# Sheet2.net
KiCad netlist of a schematic drawn in Altium Designer
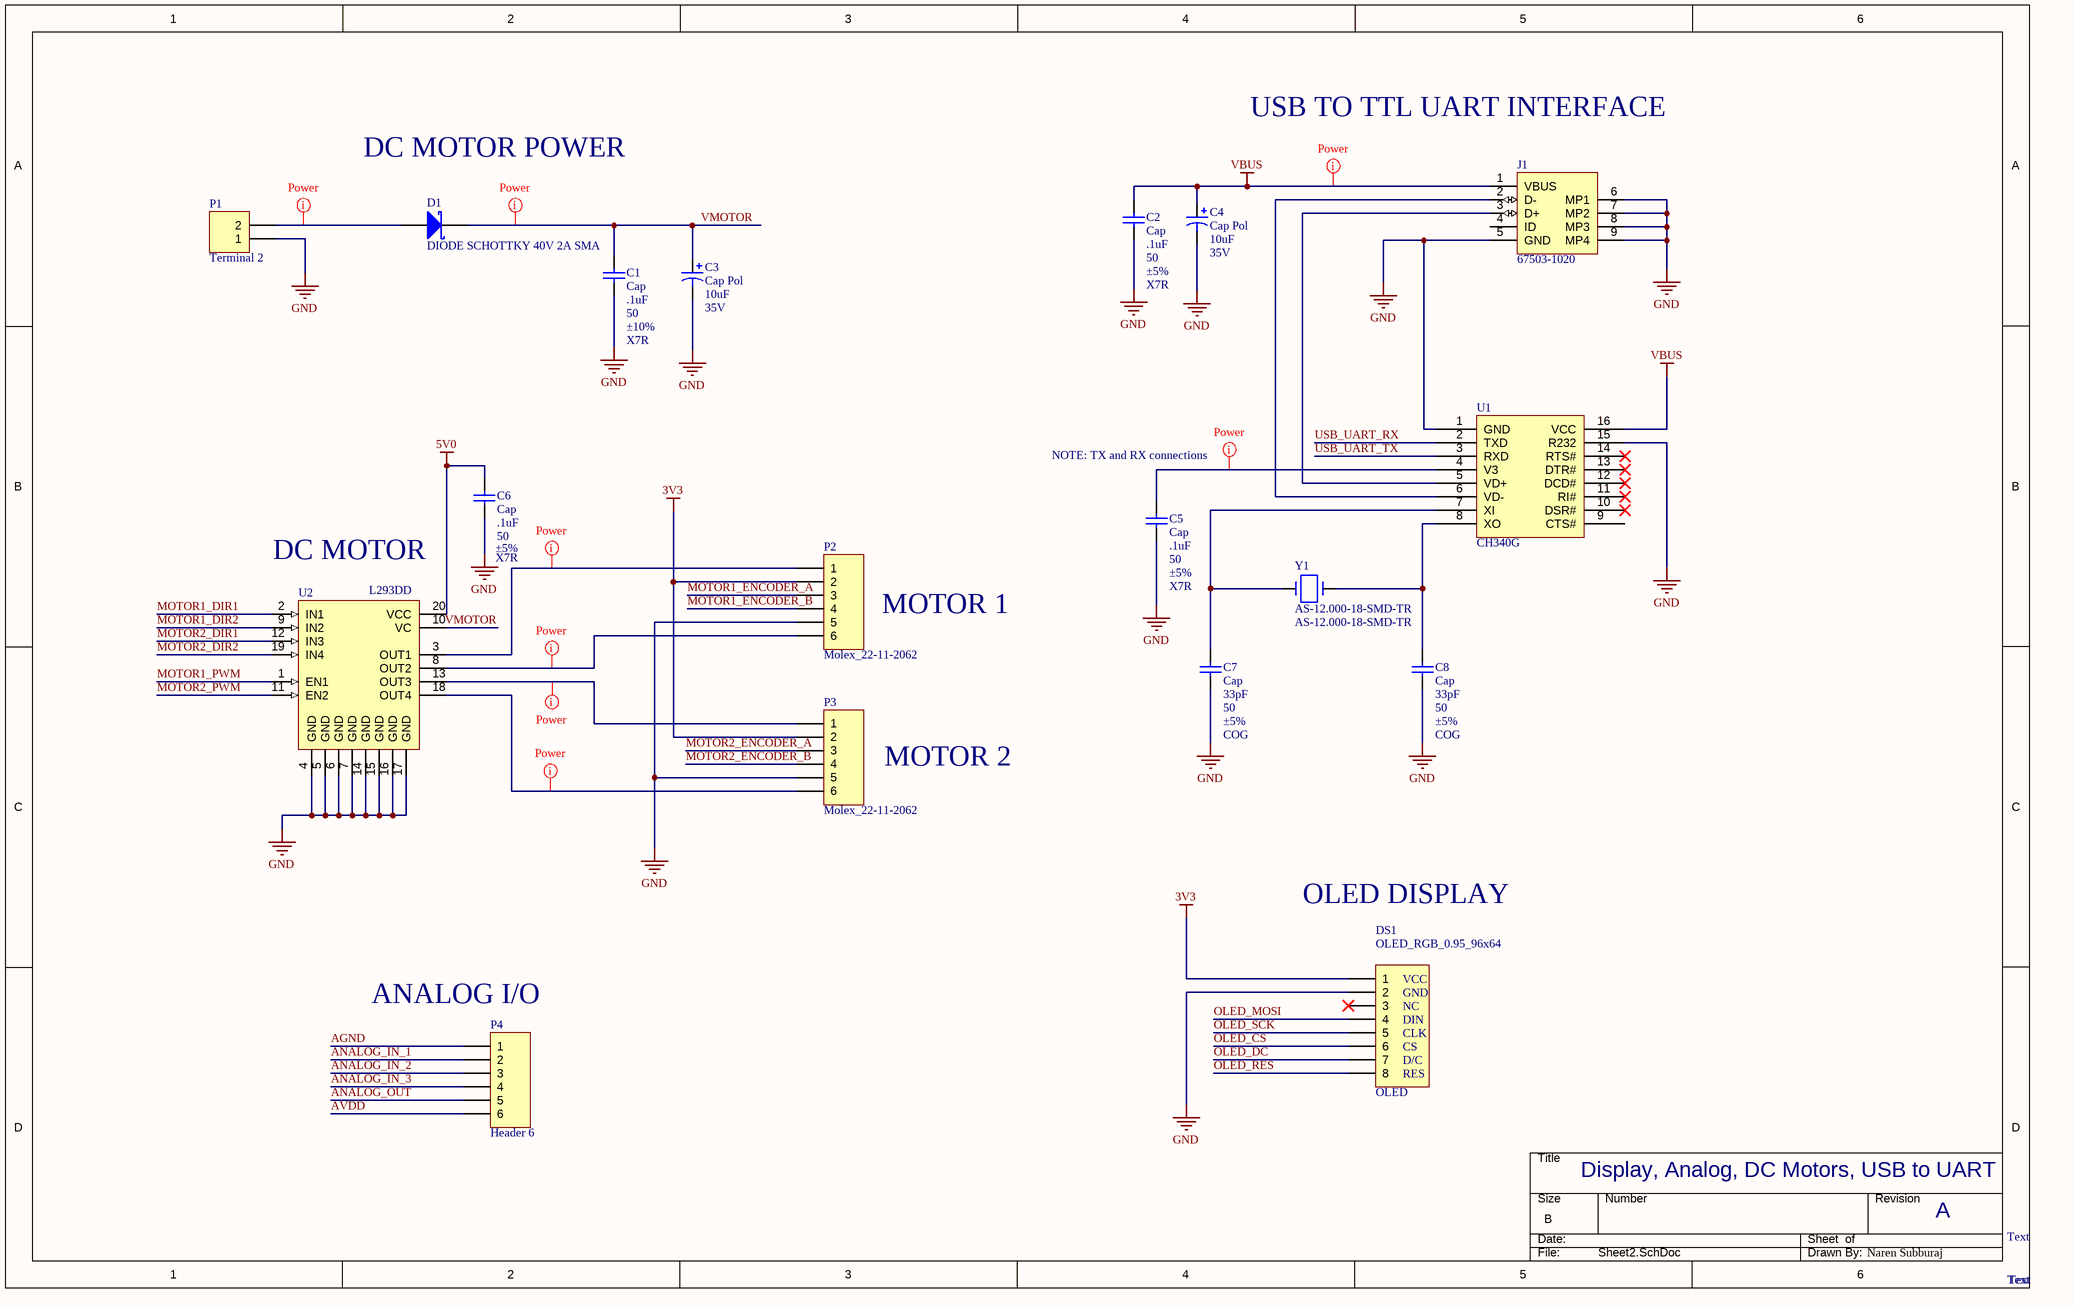
[diagram p0: Sheet2.SchDoc]

(export (version "E")
  (design (tool "Eeschema 10.0.6"))
  (components
    (comp (ref "C1")
      (value "Cap")
      (footprint "CAPC2012X09M")
      (description "CAP CER .1uF 50v X7R 0805")
      (fields
        (field (name "ALTIUM_VALUE") ".1uF")
        (field (name "WV") "50")
        (field (name "TOLERANCE") "±10%")
        (field (name "TYPE") "X7R")
        (field (name "MPN") "C0805C104K5RACTU")
      )
      (libsource (lib "esd_library") (part "CAP-X7R-.1uF-50V-±10%"))
    )
    (comp (ref "C2")
      (value "Cap")
      (footprint "CAPC2012X09M")
      (description "CAP CER .1uF 50v X7R 0805")
      (fields
        (field (name "ALTIUM_VALUE") ".1uF")
        (field (name "WV") "50")
        (field (name "TOLERANCE") "±5%")
        (field (name "TYPE") "X7R")
        (field (name "MPN") "C0805C104J5RACTU")
      )
      (libsource (lib "esd_library") (part "CAP-X7R-.1uF-50V-±5%"))
    )
    (comp (ref "C3")
      (value "Cap Pol")
      (footprint "CAPACITOR_5MM")
      (description "CAP 85C 10uF ±20% 35V WX Series Aluminum Electrolytic")
      (fields
        (field (name "ALTIUM_VALUE") "10uF")
        (field (name "VOLTAGE") "35V")
        (field (name "MPN") "UWX1V100MCL1GB")
      )
      (libsource (lib "esd_library") (part "Cap Polar-10uF-35V"))
    )
    (comp (ref "C4")
      (value "Cap Pol")
      (footprint "CAPACITOR_5MM")
      (description "CAP 85C 10uF ±20% 35V WX Series Aluminum Electrolytic")
      (fields
        (field (name "ALTIUM_VALUE") "10uF")
        (field (name "VOLTAGE") "35V")
        (field (name "MPN") "UWX1V100MCL1GB")
      )
      (libsource (lib "esd_library") (part "Cap Polar-10uF-35V"))
    )
    (comp (ref "C5")
      (value "Cap")
      (footprint "CAPC2012X09M")
      (description "CAP CER .1uF 50v X7R 0805")
      (fields
        (field (name "ALTIUM_VALUE") ".1uF")
        (field (name "WV") "50")
        (field (name "TOLERANCE") "±5%")
        (field (name "TYPE") "X7R")
        (field (name "MPN") "C0805C104J5RACTU")
      )
      (libsource (lib "esd_library") (part "CAP-X7R-.1uF-50V-±5%"))
    )
    (comp (ref "C6")
      (value "Cap")
      (footprint "CAPC2012X09M")
      (description "CAP CER .1uF 50v X7R 0805")
      (fields
        (field (name "ALTIUM_VALUE") ".1uF")
        (field (name "WV") "50")
        (field (name "TOLERANCE") "±5%")
        (field (name "TYPE") "X7R")
        (field (name "MPN") "C0805C104J5RACTU")
      )
      (libsource (lib "esd_library") (part "CAP-X7R-.1uF-50V-±5%"))
    )
    (comp (ref "C7")
      (value "Cap")
      (footprint "CAPC2012X09M")
      (description "CAP CER 33pF 50v COG 0805")
      (fields
        (field (name "ALTIUM_VALUE") "33pF")
        (field (name "WV") "50")
        (field (name "TOLERANCE") "±5%")
        (field (name "TYPE") "COG")
        (field (name "MPN") "C0805C330J5GACTU")
      )
      (libsource (lib "esd_library") (part "CAP-COG-33pF-50V-±5%"))
    )
    (comp (ref "C8")
      (value "Cap")
      (footprint "CAPC2012X09M")
      (description "CAP CER 33pF 50v COG 0805")
      (fields
        (field (name "ALTIUM_VALUE") "33pF")
        (field (name "WV") "50")
        (field (name "TOLERANCE") "±5%")
        (field (name "TYPE") "COG")
        (field (name "MPN") "C0805C330J5GACTU")
      )
      (libsource (lib "esd_library") (part "CAP-COG-33pF-50V-±5%"))
    )
    (comp (ref "D1")
      (value "DIODE SCHOTTKY 40V 2A SMA")
      (footprint "DIOM4326X23M")
      (description "Schottky Rectifier")
      (fields (field (name "MPN") "B240A-13-F"))
      (libsource (lib "esd_library") (part "DIODE SCHOTTKY 40V 2A SMA"))
    )
    (comp (ref "DS1")
      (value "OLED")
      (footprint "OLED_RGB_0.95_96x64_Waveshare")
      (description "Waveshare 0.95 inch OLED Module")
      (fields (field (name "MPN") "PPPC081LFBN-RC"))
      (libsource (lib "esd_library") (part "OLED_RGB_0.95_96x64_Waveshare"))
    )
    (comp (ref "J1")
      (value "67503-1020")
      (footprint "MOLX-67503-1020_V")
      (description "USB, MINI, SMD, RA KME04-USBMU03A01")
      (fields (field (name "MANUFACTURER") "Molex"))
      (libsource (lib "esd_library") (part "MOLX-67503-1020"))
    )
    (comp (ref "P1")
      (value "Terminal 2")
      (footprint "TYCO_282841_2")
      (description "Terminal, 2-Pin")
      (fields (field (name "MPN") "282841-2") (field (name "PUBLISHER") "Altium Limited"))
      (libsource (lib "esd_library") (part "Terminal 2"))
    )
    (comp (ref "P2")
      (value "Molex_22-11-2062")
      (footprint "MOLEX_22-11-2062")
      (description "CONN HEADER 6POS .100 VERT GOLD")
      (fields (field (name "MPN") "0022112062"))
      (libsource (lib "esd_library") (part "Molex_22-11-2062"))
    )
    (comp (ref "P3")
      (value "Molex_22-11-2062")
      (footprint "MOLEX_22-11-2062")
      (description "CONN HEADER 6POS .100 VERT GOLD")
      (fields (field (name "MPN") "0022112062"))
      (libsource (lib "esd_library") (part "Molex_22-11-2062"))
    )
    (comp (ref "P4")
      (value "Header 6")
      (footprint "HDR1X6")
      (description "Header, 6-Pin Male")
      (fields (field (name "MPN") "PEC06SFAN"))
      (libsource (lib "esd_library") (part "Header 6"))
    )
    (comp (ref "U1")
      (value "CH340G")
      (footprint "NSO16_L")
      (description "USB to serial chip")
      (libsource (lib "esd_library") (part "CH340G"))
    )
    (comp (ref "U2")
      (value "L293DD")
      (footprint "SO20_N")
      (description "IC MOTOR DRIVER PAR 20-SOIC")
      (fields (field (name "MPN") "L293DD013TR") (field (name "PUBLISHER") "Altium Limited"))
      (libsource (lib "esd_library") (part "L293DD"))
    )
    (comp (ref "Y1")
      (value "AS-12.000-18-SMD-TR")
      (footprint "HCS-49/U")
      (description "CRYSTAL 12.0000MHZ 18PF SMD")
      (fields (field (name "MPN") "AS-12.000-18-SMD-TR"))
      (libsource (lib "esd_library") (part "AS-12.000-18-SMD-TR"))
    )
  )
  (nets
    (net (code "1") (name "/AGND") (class "Default")
      (node (ref "P4") (pin "1") (pinfunction "1_1") (pintype "passive"))
    )
    (net (code "2") (name "/ANALOG_IN_1") (class "Default")
      (node (ref "P4") (pin "2") (pinfunction "2_2") (pintype "passive"))
    )
    (net (code "3") (name "/ANALOG_IN_2") (class "Default")
      (node (ref "P4") (pin "3") (pinfunction "3_3") (pintype "passive"))
    )
    (net (code "4") (name "/ANALOG_IN_3") (class "Default")
      (node (ref "P4") (pin "4") (pinfunction "4_4") (pintype "passive"))
    )
    (net (code "5") (name "/ANALOG_OUT") (class "Default")
      (node (ref "P4") (pin "5") (pinfunction "5_5") (pintype "passive"))
    )
    (net (code "6") (name "/AVDD") (class "Default")
      (node (ref "P4") (pin "6") (pinfunction "6_6") (pintype "passive"))
    )
    (net (code "7") (name "/MOTOR1_DIR1") (class "Default")
      (node (ref "U2") (pin "2") (pinfunction "IN1_2") (pintype "input"))
    )
    (net (code "8") (name "/MOTOR1_DIR2") (class "Default")
      (node (ref "U2") (pin "9") (pinfunction "IN2_9") (pintype "input"))
    )
    (net (code "9") (name "/MOTOR1_ENCODER_A") (class "Default")
      (node (ref "P2") (pin "3") (pinfunction "3_3") (pintype "passive"))
    )
    (net (code "10") (name "/MOTOR1_ENCODER_B") (class "Default")
      (node (ref "P2") (pin "4") (pinfunction "4_4") (pintype "passive"))
    )
    (net (code "11") (name "/MOTOR1_PWM") (class "Default")
      (node (ref "U2") (pin "1") (pinfunction "EN1_1") (pintype "input"))
    )
    (net (code "12") (name "/MOTOR2_DIR1") (class "Default")
      (node (ref "U2") (pin "12") (pinfunction "IN3_12") (pintype "input"))
    )
    (net (code "13") (name "/MOTOR2_DIR2") (class "Default")
      (node (ref "U2") (pin "19") (pinfunction "IN4_19") (pintype "input"))
    )
    (net (code "14") (name "/MOTOR2_ENCODER_A") (class "Default")
      (node (ref "P3") (pin "3") (pinfunction "3_3") (pintype "passive"))
    )
    (net (code "15") (name "/MOTOR2_ENCODER_B") (class "Default")
      (node (ref "P3") (pin "4") (pinfunction "4_4") (pintype "passive"))
    )
    (net (code "16") (name "/MOTOR2_PWM") (class "Default")
      (node (ref "U2") (pin "11") (pinfunction "EN2_11") (pintype "input"))
    )
    (net (code "17") (name "/OLED_CS") (class "Default")
      (node (ref "DS1") (pin "6") (pinfunction "6_6") (pintype "passive"))
    )
    (net (code "18") (name "/OLED_DC") (class "Default")
      (node (ref "DS1") (pin "7") (pinfunction "7_7") (pintype "passive"))
    )
    (net (code "19") (name "/OLED_MOSI") (class "Default")
      (node (ref "DS1") (pin "4") (pinfunction "4_4") (pintype "passive"))
    )
    (net (code "20") (name "/OLED_RES") (class "Default")
      (node (ref "DS1") (pin "8") (pinfunction "8_8") (pintype "passive"))
    )
    (net (code "21") (name "/OLED_SCK") (class "Default")
      (node (ref "DS1") (pin "5") (pinfunction "5_5") (pintype "passive"))
    )
    (net (code "22") (name "/USB_UART_RX") (class "Default")
      (node (ref "U1") (pin "2") (pinfunction "TXD_2") (pintype "passive"))
    )
    (net (code "23") (name "/USB_UART_TX") (class "Default")
      (node (ref "U1") (pin "3") (pinfunction "RXD_3") (pintype "passive"))
    )
    (net (code "24") (name "/VMOTOR") (class "Default")
      (node (ref "C1") (pin "2") (pinfunction "2_2") (pintype "passive"))
      (node (ref "C3") (pin "1") (pinfunction "1_1") (pintype "passive"))
      (node (ref "D1") (pin "1") (pinfunction "K_1") (pintype "passive"))
      (node (ref "U2") (pin "10") (pinfunction "VC_10") (pintype "power_in"))
    )
    (net (code "25") (name "3V3") (class "Default")
      (node (ref "DS1") (pin "1") (pinfunction "1_1") (pintype "passive"))
      (node (ref "P2") (pin "2") (pinfunction "2_2") (pintype "passive"))
      (node (ref "P3") (pin "2") (pinfunction "2_2") (pintype "passive"))
    )
    (net (code "26") (name "5V0") (class "Default")
      (node (ref "C6") (pin "2") (pinfunction "2_2") (pintype "passive"))
      (node (ref "U2") (pin "20") (pinfunction "VCC_20") (pintype "power_in"))
    )
    (net (code "27") (name "GND") (class "Default")
      (node (ref "C1") (pin "1") (pinfunction "1_1") (pintype "passive"))
      (node (ref "C2") (pin "2") (pinfunction "2_2") (pintype "passive"))
      (node (ref "C3") (pin "2") (pinfunction "2_2") (pintype "passive"))
      (node (ref "C4") (pin "2") (pinfunction "2_2") (pintype "passive"))
      (node (ref "C5") (pin "2") (pinfunction "2_2") (pintype "passive"))
      (node (ref "C6") (pin "1") (pinfunction "1_1") (pintype "passive"))
      (node (ref "C7") (pin "2") (pinfunction "2_2") (pintype "passive"))
      (node (ref "C8") (pin "2") (pinfunction "2_2") (pintype "passive"))
      (node (ref "DS1") (pin "2") (pinfunction "2_2") (pintype "passive"))
      (node (ref "J1") (pin "5") (pinfunction "GND_5") (pintype "power_in"))
      (node (ref "J1") (pin "6") (pinfunction "MP1_6") (pintype "passive"))
      (node (ref "J1") (pin "7") (pinfunction "MP2_7") (pintype "passive"))
      (node (ref "J1") (pin "8") (pinfunction "MP3_8") (pintype "passive"))
      (node (ref "J1") (pin "9") (pinfunction "MP4_9") (pintype "passive"))
      (node (ref "P1") (pin "1") (pinfunction "1_1") (pintype "passive"))
      (node (ref "P2") (pin "5") (pinfunction "5_5") (pintype "passive"))
      (node (ref "P3") (pin "5") (pinfunction "5_5") (pintype "passive"))
      (node (ref "U1") (pin "1") (pinfunction "GND_1") (pintype "passive"))
      (node (ref "U1") (pin "15") (pinfunction "R232_15") (pintype "passive"))
      (node (ref "U2") (pin "14") (pinfunction "GND_14") (pintype "power_in"))
      (node (ref "U2") (pin "15") (pinfunction "GND_15") (pintype "power_in"))
      (node (ref "U2") (pin "16") (pinfunction "GND_16") (pintype "power_in"))
      (node (ref "U2") (pin "17") (pinfunction "GND_17") (pintype "power_in"))
      (node (ref "U2") (pin "4") (pinfunction "GND_4") (pintype "power_in"))
      (node (ref "U2") (pin "5") (pinfunction "GND_5") (pintype "power_in"))
      (node (ref "U2") (pin "6") (pinfunction "GND_6") (pintype "power_in"))
      (node (ref "U2") (pin "7") (pinfunction "GND_7") (pintype "power_in"))
    )
    (net (code "28") (name "Net-(D1-A)") (class "Default")
      (node (ref "D1") (pin "2") (pinfunction "A_2") (pintype "passive"))
      (node (ref "P1") (pin "2") (pinfunction "2_2") (pintype "passive"))
    )
    (net (code "29") (name "Net-(J1-D+)") (class "Default")
      (node (ref "J1") (pin "3") (pinfunction "D+_3") (pintype "bidirectional"))
      (node (ref "U1") (pin "5") (pinfunction "VD+_5") (pintype "passive"))
    )
    (net (code "30") (name "Net-(J1-D-)") (class "Default")
      (node (ref "J1") (pin "2") (pinfunction "D-_2") (pintype "bidirectional"))
      (node (ref "U1") (pin "6") (pinfunction "VD-_6") (pintype "passive"))
    )
    (net (code "31") (name "Net-(U1-V3)") (class "Default")
      (node (ref "C5") (pin "1") (pinfunction "1_1") (pintype "passive"))
      (node (ref "U1") (pin "4") (pinfunction "V3_4") (pintype "passive"))
    )
    (net (code "32") (name "Net-(U1-XI)") (class "Default")
      (node (ref "C7") (pin "1") (pinfunction "1_1") (pintype "passive"))
      (node (ref "U1") (pin "7") (pinfunction "XI_7") (pintype "passive"))
      (node (ref "Y1") (pin "1") (pinfunction "1_1") (pintype "passive"))
    )
    (net (code "33") (name "Net-(U1-XO)") (class "Default")
      (node (ref "C8") (pin "1") (pinfunction "1_1") (pintype "passive"))
      (node (ref "U1") (pin "8") (pinfunction "XO_8") (pintype "passive"))
      (node (ref "Y1") (pin "2") (pinfunction "2_2") (pintype "passive"))
    )
    (net (code "34") (name "Net-(U2-OUT1)") (class "Default")
      (node (ref "P2") (pin "1") (pinfunction "1_1") (pintype "passive"))
      (node (ref "U2") (pin "3") (pinfunction "OUT1_3") (pintype "tri_state"))
    )
    (net (code "35") (name "Net-(U2-OUT2)") (class "Default")
      (node (ref "P2") (pin "6") (pinfunction "6_6") (pintype "passive"))
      (node (ref "U2") (pin "8") (pinfunction "OUT2_8") (pintype "tri_state"))
    )
    (net (code "36") (name "Net-(U2-OUT3)") (class "Default")
      (node (ref "P3") (pin "1") (pinfunction "1_1") (pintype "passive"))
      (node (ref "U2") (pin "13") (pinfunction "OUT3_13") (pintype "tri_state"))
    )
    (net (code "37") (name "Net-(U2-OUT4)") (class "Default")
      (node (ref "P3") (pin "6") (pinfunction "6_6") (pintype "passive"))
      (node (ref "U2") (pin "18") (pinfunction "OUT4_18") (pintype "tri_state"))
    )
    (net (code "38") (name "VBUS") (class "Default")
      (node (ref "C2") (pin "1") (pinfunction "1_1") (pintype "passive"))
      (node (ref "C4") (pin "1") (pinfunction "1_1") (pintype "passive"))
      (node (ref "J1") (pin "1") (pinfunction "VBUS_1") (pintype "power_in"))
      (node (ref "U1") (pin "16") (pinfunction "VCC_16") (pintype "passive"))
    )
    (net (code "39") (name "unconnected-(DS1-Pad3)") (class "Default")
      (node (ref "DS1") (pin "3") (pinfunction "3_3") (pintype "passive+no_connect"))
    )
    (net (code "40") (name "unconnected-(J1-ID-Pad4)") (class "Default")
      (node (ref "J1") (pin "4") (pinfunction "ID_4") (pintype "passive"))
    )
    (net (code "41") (name "unconnected-(U1-CTS#-Pad9)") (class "Default")
      (node (ref "U1") (pin "9") (pinfunction "CTS#_9") (pintype "passive"))
    )
    (net (code "42") (name "unconnected-(U1-DCD#-Pad12)") (class "Default")
      (node (ref "U1") (pin "12") (pinfunction "DCD#_12") (pintype "passive+no_connect"))
    )
    (net (code "43") (name "unconnected-(U1-DSR#-Pad10)") (class "Default")
      (node (ref "U1") (pin "10") (pinfunction "DSR#_10") (pintype "passive+no_connect"))
    )
    (net (code "44") (name "unconnected-(U1-DTR#-Pad13)") (class "Default")
      (node (ref "U1") (pin "13") (pinfunction "DTR#_13") (pintype "passive+no_connect"))
    )
    (net (code "45") (name "unconnected-(U1-RI#-Pad11)") (class "Default")
      (node (ref "U1") (pin "11") (pinfunction "RI#_11") (pintype "passive+no_connect"))
    )
    (net (code "46") (name "unconnected-(U1-RTS#-Pad14)") (class "Default")
      (node (ref "U1") (pin "14") (pinfunction "RTS#_14") (pintype "passive+no_connect"))
    )
  )
)
